# Elektrotechnika.net
KiCad netlist of a schematic drawn in EasyEDA Pro
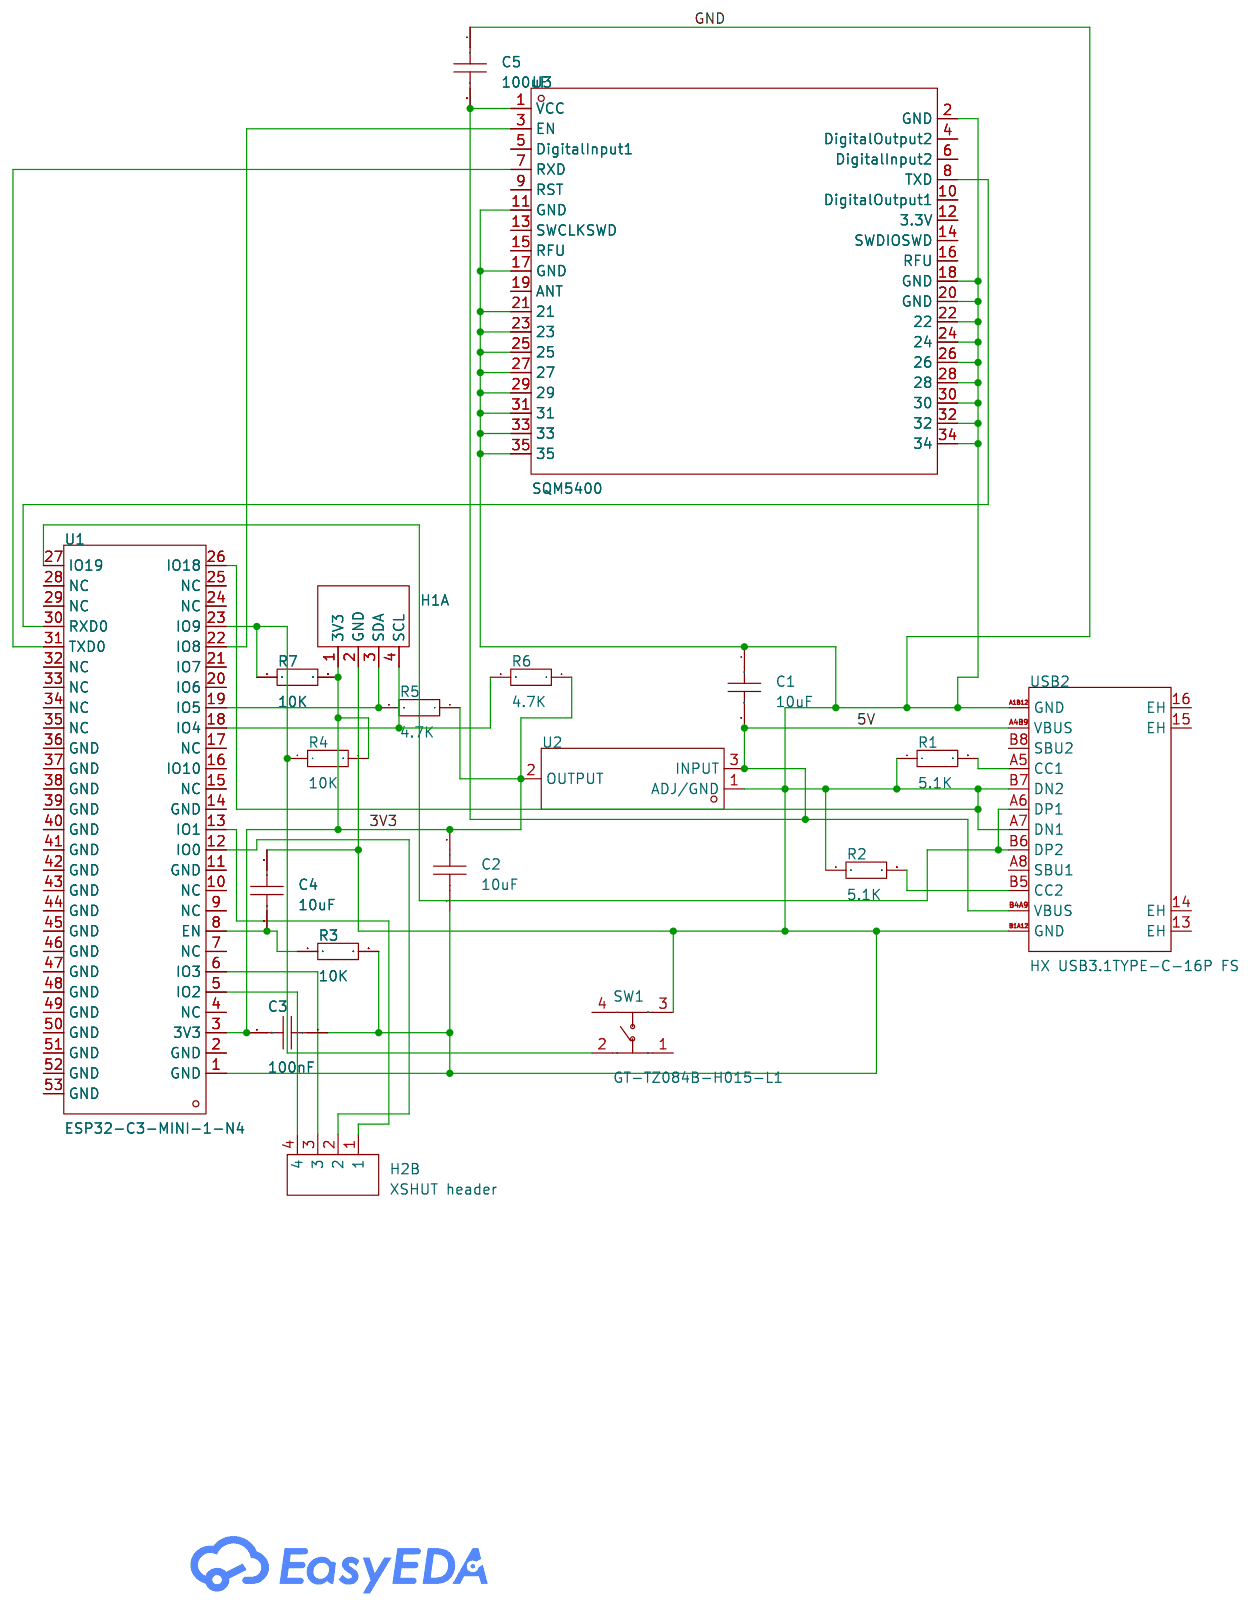
[diagram p0: schematic sheet]

(export (version "E")
  (design (tool "Eeschema 10.0.6"))
  (components
    (comp (ref "C1")
      (value "10uF")
      (footprint "easyedapro:C0603")
      (libsource (lib "easyedapro") (part "CAP"))
    )
    (comp (ref "C2")
      (value "10uF")
      (footprint "easyedapro:C0603")
      (libsource (lib "easyedapro") (part "CAP"))
    )
    (comp (ref "C3")
      (value "100nF")
      (footprint "easyedapro:C0603")
      (libsource (lib "easyedapro") (part "CAP"))
    )
    (comp (ref "C4")
      (value "10uF")
      (footprint "easyedapro:C0603")
      (libsource (lib "easyedapro") (part "CAP"))
    )
    (comp (ref "C5")
      (value "100uF")
      (footprint "easyedapro:C0603")
      (libsource (lib "easyedapro") (part "CAP"))
    )
    (comp (ref "H1")
      (value "HX PH254-01-04-Z-L11.5 straight pin header")
      (footprint "easyedapro:HDR-TH_4P-HX-PH254-01-04-Z-L11.5")
      (fields (field (name "Manufacturer") "hanxia(韩下)"))
      (libsource (lib "easyedapro") (part "HX PH254-01-04-Z-L11.5 STRAIGHT PIN HEADER"))
    )
    (comp (ref "H2")
      (value "XSHUT header")
      (footprint "easyedapro:HDR-TH_4P-HX-PH254-01-04-Z-L11.5")
      (fields
        (field (name "Manufacturer Part") "HX PH254-01-04-Z-L11.5 straight pin header")
        (field (name "Manufacturer") "hanxia(韩下)")
      )
      (libsource (lib "easyedapro") (part "HX PH254-01-04-Z-L11.5 STRAIGHT PIN HEADER"))
    )
    (comp (ref "R1")
      (value "5.1K")
      (footprint "easyedapro:R0603")
      (libsource (lib "easyedapro") (part "Res"))
    )
    (comp (ref "R2")
      (value "5.1K")
      (footprint "easyedapro:R0603")
      (libsource (lib "easyedapro") (part "Res"))
    )
    (comp (ref "R3") (value "10K") (footprint "easyedapro:R0603") (libsource (lib "easyedapro") (part "Res")))
    (comp (ref "R4") (value "10K") (footprint "easyedapro:R0603") (libsource (lib "easyedapro") (part "Res")))
    (comp (ref "R5")
      (value "4.7K")
      (footprint "easyedapro:R0603")
      (libsource (lib "easyedapro") (part "Res"))
    )
    (comp (ref "R6")
      (value "4.7K")
      (footprint "easyedapro:R0603")
      (libsource (lib "easyedapro") (part "Res"))
    )
    (comp (ref "R7") (value "10K") (footprint "easyedapro:R0603") (libsource (lib "easyedapro") (part "Res")))
    (comp (ref "SW1")
      (value "GT-TZ084B-H015-L1")
      (footprint "easyedapro:SW-SMD_4P-L5.2-W5.2-P3.70-LS6.4")
      (fields (field (name "Manufacturer") "G-Switch(品赞)"))
      (libsource (lib "easyedapro") (part "GT-TZ084B-H015-L1"))
    )
    (comp (ref "U1")
      (value "ESP32-C3-MINI-1-N4")
      (footprint "easyedapro:WIFIM-SMD_ESP32-C3-MINI-1")
      (fields (field (name "Manufacturer") "ESPRESSIF(乐鑫)"))
      (libsource (lib "easyedapro") (part "ESP32-C3-MINI-1-N4"))
    )
    (comp (ref "U2")
      (value "AMS1117-3.3")
      (footprint "easyedapro:TO-252-2_L6.6-W5.6-P2.3-LS9.7")
      (fields (field (name "Manufacturer") "YONGYUTAI(永裕泰)"))
      (libsource (lib "easyedapro") (part "AMS1117-3.3_C41414107"))
    )
    (comp (ref "U3")
      (value "SQM5400")
      (footprint "easyedapro:COMM-SMD_35P-L21.0-W21.0_SQM5400")
      (fields (field (name "Manufacturer") "SILION(芯联创展)"))
      (libsource (lib "easyedapro") (part "SQM5400"))
    )
    (comp (ref "USB2")
      (value "HX USB3.1TYPE-C-16P FS")
      (footprint "easyedapro:USB-C-SMD_HX-USB3.1TYPE-C-16P-FS")
      (fields (field (name "Manufacturer") "hanxia(韩下)"))
      (libsource (lib "easyedapro") (part "HX USB3.1TYPE-C-16P FS"))
    )
  )
  (nets
    (net (code "1") (name "/3V3") (class "Default")
      (node (ref "C2") (pin "1") (pinfunction "1_1") (pintype "input"))
      (node (ref "C3") (pin "2") (pinfunction "2_2") (pintype "input"))
      (node (ref "H1") (pin "1") (pinfunction "3V3_1") (pintype "unspecified"))
      (node (ref "R4") (pin "2") (pinfunction "2_2") (pintype "input"))
      (node (ref "R5") (pin "1") (pinfunction "1_1") (pintype "input"))
      (node (ref "R6") (pin "1") (pinfunction "1_1") (pintype "input"))
      (node (ref "R7") (pin "2") (pinfunction "2_2") (pintype "input"))
      (node (ref "U1") (pin "3") (pinfunction "3V3_3") (pintype "unspecified"))
      (node (ref "U2") (pin "2") (pinfunction "OUTPUT_2") (pintype "unspecified"))
    )
    (net (code "2") (name "/5V") (class "Default")
      (node (ref "C1") (pin "2") (pinfunction "2_2") (pintype "input"))
      (node (ref "C5") (pin "2") (pinfunction "2_2") (pintype "input"))
      (node (ref "U2") (pin "3") (pinfunction "INPUT_3") (pintype "unspecified"))
      (node (ref "U3") (pin "1") (pinfunction "VCC_1") (pintype "unspecified"))
      (node (ref "USB2") (pin "A4B9") (pinfunction "VBUS_A4B9") (pintype "unspecified"))
      (node (ref "USB2") (pin "B4A9") (pinfunction "VBUS_B4A9") (pintype "unspecified"))
    )
    (net (code "3") (name "/GND") (class "Default")
      (node (ref "C1") (pin "1") (pinfunction "1_1") (pintype "input"))
      (node (ref "C2") (pin "2") (pinfunction "2_2") (pintype "input"))
      (node (ref "C3") (pin "1") (pinfunction "1_1") (pintype "input"))
      (node (ref "C4") (pin "1") (pinfunction "1_1") (pintype "input"))
      (node (ref "C5") (pin "1") (pinfunction "1_1") (pintype "input"))
      (node (ref "H1") (pin "2") (pinfunction "GND_2") (pintype "unspecified"))
      (node (ref "R1") (pin "1") (pinfunction "1_1") (pintype "input"))
      (node (ref "R2") (pin "1") (pinfunction "1_1") (pintype "input"))
      (node (ref "R3") (pin "2") (pinfunction "2_2") (pintype "input"))
      (node (ref "SW1") (pin "3") (pinfunction "3_3") (pintype "unspecified"))
      (node (ref "U1") (pin "1") (pinfunction "GND_1") (pintype "unspecified"))
      (node (ref "U1") (pin "26") (pinfunction "IO18_26") (pintype "unspecified"))
      (node (ref "U2") (pin "1") (pinfunction "ADJ/GND_1") (pintype "unspecified"))
      (node (ref "U3") (pin "11") (pinfunction "GND_11") (pintype "unspecified"))
      (node (ref "U3") (pin "17") (pinfunction "GND_17") (pintype "unspecified"))
      (node (ref "U3") (pin "18") (pinfunction "GND_18") (pintype "unspecified"))
      (node (ref "U3") (pin "2") (pinfunction "GND_2") (pintype "unspecified"))
      (node (ref "U3") (pin "20") (pinfunction "GND_20") (pintype "unspecified"))
      (node (ref "U3") (pin "21") (pinfunction "21_21") (pintype "unspecified"))
      (node (ref "U3") (pin "22") (pinfunction "22_22") (pintype "unspecified"))
      (node (ref "U3") (pin "23") (pinfunction "23_23") (pintype "unspecified"))
      (node (ref "U3") (pin "24") (pinfunction "24_24") (pintype "unspecified"))
      (node (ref "U3") (pin "25") (pinfunction "25_25") (pintype "unspecified"))
      (node (ref "U3") (pin "26") (pinfunction "26_26") (pintype "unspecified"))
      (node (ref "U3") (pin "27") (pinfunction "27_27") (pintype "unspecified"))
      (node (ref "U3") (pin "28") (pinfunction "28_28") (pintype "unspecified"))
      (node (ref "U3") (pin "29") (pinfunction "29_29") (pintype "unspecified"))
      (node (ref "U3") (pin "30") (pinfunction "30_30") (pintype "unspecified"))
      (node (ref "U3") (pin "31") (pinfunction "31_31") (pintype "unspecified"))
      (node (ref "U3") (pin "32") (pinfunction "32_32") (pintype "unspecified"))
      (node (ref "U3") (pin "33") (pinfunction "33_33") (pintype "unspecified"))
      (node (ref "U3") (pin "34") (pinfunction "34_34") (pintype "unspecified"))
      (node (ref "U3") (pin "35") (pinfunction "35_35") (pintype "unspecified"))
      (node (ref "USB2") (pin "A1B12") (pinfunction "GND_A1B12") (pintype "unspecified"))
      (node (ref "USB2") (pin "A7") (pinfunction "DN1_A7") (pintype "unspecified"))
      (node (ref "USB2") (pin "B1A12") (pinfunction "GND_B1A12") (pintype "unspecified"))
      (node (ref "USB2") (pin "B7") (pinfunction "DN2_B7") (pintype "unspecified"))
    )
    (net (code "4") (name "Net-(H1A-SCL)") (class "Default")
      (node (ref "H1") (pin "4") (pinfunction "SCL_4") (pintype "unspecified"))
      (node (ref "R6") (pin "2") (pinfunction "2_2") (pintype "input"))
      (node (ref "U1") (pin "18") (pinfunction "IO4_18") (pintype "unspecified"))
    )
    (net (code "5") (name "Net-(H1A-SDA)") (class "Default")
      (node (ref "H1") (pin "3") (pinfunction "SDA_3") (pintype "unspecified"))
      (node (ref "R5") (pin "2") (pinfunction "2_2") (pintype "input"))
      (node (ref "U1") (pin "19") (pinfunction "IO5_19") (pintype "unspecified"))
    )
    (net (code "6") (name "Net-(U1-EN)") (class "Default")
      (node (ref "C4") (pin "2") (pinfunction "2_2") (pintype "input"))
      (node (ref "R3") (pin "1") (pinfunction "1_1") (pintype "input"))
      (node (ref "U1") (pin "8") (pinfunction "EN_8") (pintype "unspecified"))
    )
    (net (code "7") (name "Net-(U1-IO0)") (class "Default")
      (node (ref "H2") (pin "2") (pinfunction "2_2") (pintype "unspecified"))
      (node (ref "U1") (pin "12") (pinfunction "IO0_12") (pintype "unspecified"))
    )
    (net (code "8") (name "Net-(U1-IO1)") (class "Default")
      (node (ref "H2") (pin "1") (pinfunction "1_1") (pintype "unspecified"))
      (node (ref "U1") (pin "13") (pinfunction "IO1_13") (pintype "unspecified"))
    )
    (net (code "9") (name "Net-(U1-IO2)") (class "Default")
      (node (ref "H2") (pin "4") (pinfunction "4_4") (pintype "unspecified"))
      (node (ref "U1") (pin "5") (pinfunction "IO2_5") (pintype "unspecified"))
    )
    (net (code "10") (name "Net-(U1-IO3)") (class "Default")
      (node (ref "H2") (pin "3") (pinfunction "3_3") (pintype "unspecified"))
      (node (ref "U1") (pin "6") (pinfunction "IO3_6") (pintype "unspecified"))
    )
    (net (code "11") (name "Net-(U1-IO8)") (class "Default")
      (node (ref "U1") (pin "22") (pinfunction "IO8_22") (pintype "unspecified"))
      (node (ref "U3") (pin "3") (pinfunction "EN_3") (pintype "unspecified"))
    )
    (net (code "12") (name "Net-(U1-IO9)") (class "Default")
      (node (ref "R4") (pin "1") (pinfunction "1_1") (pintype "input"))
      (node (ref "R7") (pin "1") (pinfunction "1_1") (pintype "input"))
      (node (ref "SW1") (pin "2") (pinfunction "2_2") (pintype "unspecified"))
      (node (ref "U1") (pin "23") (pinfunction "IO9_23") (pintype "unspecified"))
    )
    (net (code "13") (name "Net-(U1-IO19)") (class "Default")
      (node (ref "U1") (pin "27") (pinfunction "IO19_27") (pintype "unspecified"))
      (node (ref "USB2") (pin "A6") (pinfunction "DP1_A6") (pintype "unspecified"))
      (node (ref "USB2") (pin "B6") (pinfunction "DP2_B6") (pintype "unspecified"))
    )
    (net (code "14") (name "Net-(U1-RXD0)") (class "Default")
      (node (ref "U1") (pin "30") (pinfunction "RXD0_30") (pintype "unspecified"))
      (node (ref "U3") (pin "8") (pinfunction "TXD_8") (pintype "unspecified"))
    )
    (net (code "15") (name "Net-(U1-TXD0)") (class "Default")
      (node (ref "U1") (pin "31") (pinfunction "TXD0_31") (pintype "unspecified"))
      (node (ref "U3") (pin "7") (pinfunction "RXD_7") (pintype "unspecified"))
    )
    (net (code "16") (name "Net-(USB2-CC1)") (class "Default")
      (node (ref "R1") (pin "2") (pinfunction "2_2") (pintype "input"))
      (node (ref "USB2") (pin "A5") (pinfunction "CC1_A5") (pintype "unspecified"))
    )
    (net (code "17") (name "Net-(USB2-CC2)") (class "Default")
      (node (ref "R2") (pin "2") (pinfunction "2_2") (pintype "input"))
      (node (ref "USB2") (pin "B5") (pinfunction "CC2_B5") (pintype "unspecified"))
    )
    (net (code "18") (name "unconnected-(SW1-Pad1)") (class "Default")
      (node (ref "SW1") (pin "1") (pinfunction "1_1") (pintype "unspecified"))
    )
    (net (code "19") (name "unconnected-(SW1-Pad4)") (class "Default")
      (node (ref "SW1") (pin "4") (pinfunction "4_4") (pintype "unspecified"))
    )
    (net (code "20") (name "unconnected-(U1-GND-Pad2)") (class "Default")
      (node (ref "U1") (pin "2") (pinfunction "GND_2") (pintype "unspecified"))
    )
    (net (code "21") (name "unconnected-(U1-GND-Pad11)") (class "Default")
      (node (ref "U1") (pin "11") (pinfunction "GND_11") (pintype "unspecified"))
    )
    (net (code "22") (name "unconnected-(U1-GND-Pad14)") (class "Default")
      (node (ref "U1") (pin "14") (pinfunction "GND_14") (pintype "unspecified"))
    )
    (net (code "23") (name "unconnected-(U1-GND-Pad36)") (class "Default")
      (node (ref "U1") (pin "36") (pinfunction "GND_36") (pintype "unspecified"))
    )
    (net (code "24") (name "unconnected-(U1-GND-Pad37)") (class "Default")
      (node (ref "U1") (pin "37") (pinfunction "GND_37") (pintype "unspecified"))
    )
    (net (code "25") (name "unconnected-(U1-GND-Pad38)") (class "Default")
      (node (ref "U1") (pin "38") (pinfunction "GND_38") (pintype "unspecified"))
    )
    (net (code "26") (name "unconnected-(U1-GND-Pad39)") (class "Default")
      (node (ref "U1") (pin "39") (pinfunction "GND_39") (pintype "unspecified"))
    )
    (net (code "27") (name "unconnected-(U1-GND-Pad40)") (class "Default")
      (node (ref "U1") (pin "40") (pinfunction "GND_40") (pintype "unspecified"))
    )
    (net (code "28") (name "unconnected-(U1-GND-Pad41)") (class "Default")
      (node (ref "U1") (pin "41") (pinfunction "GND_41") (pintype "unspecified"))
    )
    (net (code "29") (name "unconnected-(U1-GND-Pad42)") (class "Default")
      (node (ref "U1") (pin "42") (pinfunction "GND_42") (pintype "unspecified"))
    )
    (net (code "30") (name "unconnected-(U1-GND-Pad43)") (class "Default")
      (node (ref "U1") (pin "43") (pinfunction "GND_43") (pintype "unspecified"))
    )
    (net (code "31") (name "unconnected-(U1-GND-Pad44)") (class "Default")
      (node (ref "U1") (pin "44") (pinfunction "GND_44") (pintype "unspecified"))
    )
    (net (code "32") (name "unconnected-(U1-GND-Pad45)") (class "Default")
      (node (ref "U1") (pin "45") (pinfunction "GND_45") (pintype "unspecified"))
    )
    (net (code "33") (name "unconnected-(U1-GND-Pad46)") (class "Default")
      (node (ref "U1") (pin "46") (pinfunction "GND_46") (pintype "unspecified"))
    )
    (net (code "34") (name "unconnected-(U1-GND-Pad47)") (class "Default")
      (node (ref "U1") (pin "47") (pinfunction "GND_47") (pintype "unspecified"))
    )
    (net (code "35") (name "unconnected-(U1-GND-Pad48)") (class "Default")
      (node (ref "U1") (pin "48") (pinfunction "GND_48") (pintype "unspecified"))
    )
    (net (code "36") (name "unconnected-(U1-GND-Pad49)") (class "Default")
      (node (ref "U1") (pin "49") (pinfunction "GND_49") (pintype "unspecified"))
    )
    (net (code "37") (name "unconnected-(U1-GND-Pad50)") (class "Default")
      (node (ref "U1") (pin "50") (pinfunction "GND_50") (pintype "unspecified"))
    )
    (net (code "38") (name "unconnected-(U1-GND-Pad51)") (class "Default")
      (node (ref "U1") (pin "51") (pinfunction "GND_51") (pintype "unspecified"))
    )
    (net (code "39") (name "unconnected-(U1-GND-Pad52)") (class "Default")
      (node (ref "U1") (pin "52") (pinfunction "GND_52") (pintype "unspecified"))
    )
    (net (code "40") (name "unconnected-(U1-GND-Pad53)") (class "Default")
      (node (ref "U1") (pin "53") (pinfunction "GND_53") (pintype "unspecified"))
    )
    (net (code "41") (name "unconnected-(U1-IO6-Pad20)") (class "Default")
      (node (ref "U1") (pin "20") (pinfunction "IO6_20") (pintype "unspecified"))
    )
    (net (code "42") (name "unconnected-(U1-IO7-Pad21)") (class "Default")
      (node (ref "U1") (pin "21") (pinfunction "IO7_21") (pintype "unspecified"))
    )
    (net (code "43") (name "unconnected-(U1-IO10-Pad16)") (class "Default")
      (node (ref "U1") (pin "16") (pinfunction "IO10_16") (pintype "unspecified"))
    )
    (net (code "44") (name "unconnected-(U1-NC-Pad4)") (class "Default")
      (node (ref "U1") (pin "4") (pinfunction "NC_4") (pintype "unspecified"))
    )
    (net (code "45") (name "unconnected-(U1-NC-Pad7)") (class "Default")
      (node (ref "U1") (pin "7") (pinfunction "NC_7") (pintype "unspecified"))
    )
    (net (code "46") (name "unconnected-(U1-NC-Pad9)") (class "Default")
      (node (ref "U1") (pin "9") (pinfunction "NC_9") (pintype "unspecified"))
    )
    (net (code "47") (name "unconnected-(U1-NC-Pad10)") (class "Default")
      (node (ref "U1") (pin "10") (pinfunction "NC_10") (pintype "unspecified"))
    )
    (net (code "48") (name "unconnected-(U1-NC-Pad15)") (class "Default")
      (node (ref "U1") (pin "15") (pinfunction "NC_15") (pintype "unspecified"))
    )
    (net (code "49") (name "unconnected-(U1-NC-Pad17)") (class "Default")
      (node (ref "U1") (pin "17") (pinfunction "NC_17") (pintype "unspecified"))
    )
    (net (code "50") (name "unconnected-(U1-NC-Pad24)") (class "Default")
      (node (ref "U1") (pin "24") (pinfunction "NC_24") (pintype "unspecified"))
    )
    (net (code "51") (name "unconnected-(U1-NC-Pad25)") (class "Default")
      (node (ref "U1") (pin "25") (pinfunction "NC_25") (pintype "unspecified"))
    )
    (net (code "52") (name "unconnected-(U1-NC-Pad28)") (class "Default")
      (node (ref "U1") (pin "28") (pinfunction "NC_28") (pintype "unspecified"))
    )
    (net (code "53") (name "unconnected-(U1-NC-Pad29)") (class "Default")
      (node (ref "U1") (pin "29") (pinfunction "NC_29") (pintype "unspecified"))
    )
    (net (code "54") (name "unconnected-(U1-NC-Pad32)") (class "Default")
      (node (ref "U1") (pin "32") (pinfunction "NC_32") (pintype "unspecified"))
    )
    (net (code "55") (name "unconnected-(U1-NC-Pad33)") (class "Default")
      (node (ref "U1") (pin "33") (pinfunction "NC_33") (pintype "unspecified"))
    )
    (net (code "56") (name "unconnected-(U1-NC-Pad34)") (class "Default")
      (node (ref "U1") (pin "34") (pinfunction "NC_34") (pintype "unspecified"))
    )
    (net (code "57") (name "unconnected-(U1-NC-Pad35)") (class "Default")
      (node (ref "U1") (pin "35") (pinfunction "NC_35") (pintype "unspecified"))
    )
    (net (code "58") (name "unconnected-(U3-3.3V-Pad12)") (class "Default")
      (node (ref "U3") (pin "12") (pinfunction "3.3V_12") (pintype "unspecified"))
    )
    (net (code "59") (name "unconnected-(U3-ANT-Pad19)") (class "Default")
      (node (ref "U3") (pin "19") (pinfunction "ANT_19") (pintype "unspecified"))
    )
    (net (code "60") (name "unconnected-(U3-DigitalInput1-Pad5)") (class "Default")
      (node (ref "U3") (pin "5") (pinfunction "DigitalInput1_5") (pintype "unspecified"))
    )
    (net (code "61") (name "unconnected-(U3-DigitalInput2-Pad6)") (class "Default")
      (node (ref "U3") (pin "6") (pinfunction "DigitalInput2_6") (pintype "unspecified"))
    )
    (net (code "62") (name "unconnected-(U3-DigitalOutput1-Pad10)") (class "Default")
      (node (ref "U3") (pin "10") (pinfunction "DigitalOutput1_10") (pintype "unspecified"))
    )
    (net (code "63") (name "unconnected-(U3-DigitalOutput2-Pad4)") (class "Default")
      (node (ref "U3") (pin "4") (pinfunction "DigitalOutput2_4") (pintype "unspecified"))
    )
    (net (code "64") (name "unconnected-(U3-RFU-Pad15)") (class "Default")
      (node (ref "U3") (pin "15") (pinfunction "RFU_15") (pintype "unspecified"))
    )
    (net (code "65") (name "unconnected-(U3-RFU-Pad16)") (class "Default")
      (node (ref "U3") (pin "16") (pinfunction "RFU_16") (pintype "unspecified"))
    )
    (net (code "66") (name "unconnected-(U3-RST-Pad9)") (class "Default")
      (node (ref "U3") (pin "9") (pinfunction "RST_9") (pintype "unspecified"))
    )
    (net (code "67") (name "unconnected-(U3-SWCLKSWD-Pad13)") (class "Default")
      (node (ref "U3") (pin "13") (pinfunction "SWCLKSWD_13") (pintype "unspecified"))
    )
    (net (code "68") (name "unconnected-(U3-SWDIOSWD-Pad14)") (class "Default")
      (node (ref "U3") (pin "14") (pinfunction "SWDIOSWD_14") (pintype "unspecified"))
    )
    (net (code "69") (name "unconnected-(USB2-EH-Pad13)") (class "Default")
      (node (ref "USB2") (pin "13") (pinfunction "EH_13") (pintype "unspecified"))
    )
    (net (code "70") (name "unconnected-(USB2-EH-Pad14)") (class "Default")
      (node (ref "USB2") (pin "14") (pinfunction "EH_14") (pintype "unspecified"))
    )
    (net (code "71") (name "unconnected-(USB2-EH-Pad15)") (class "Default")
      (node (ref "USB2") (pin "15") (pinfunction "EH_15") (pintype "unspecified"))
    )
    (net (code "72") (name "unconnected-(USB2-EH-Pad16)") (class "Default")
      (node (ref "USB2") (pin "16") (pinfunction "EH_16") (pintype "unspecified"))
    )
    (net (code "73") (name "unconnected-(USB2-SBU1-PadA8)") (class "Default")
      (node (ref "USB2") (pin "A8") (pinfunction "SBU1_A8") (pintype "unspecified"))
    )
    (net (code "74") (name "unconnected-(USB2-SBU2-PadB8)") (class "Default")
      (node (ref "USB2") (pin "B8") (pinfunction "SBU2_B8") (pintype "unspecified"))
    )
  )
)
